# KTIR-FRONT.net
KiCad netlist of a schematic drawn in Altium Designer
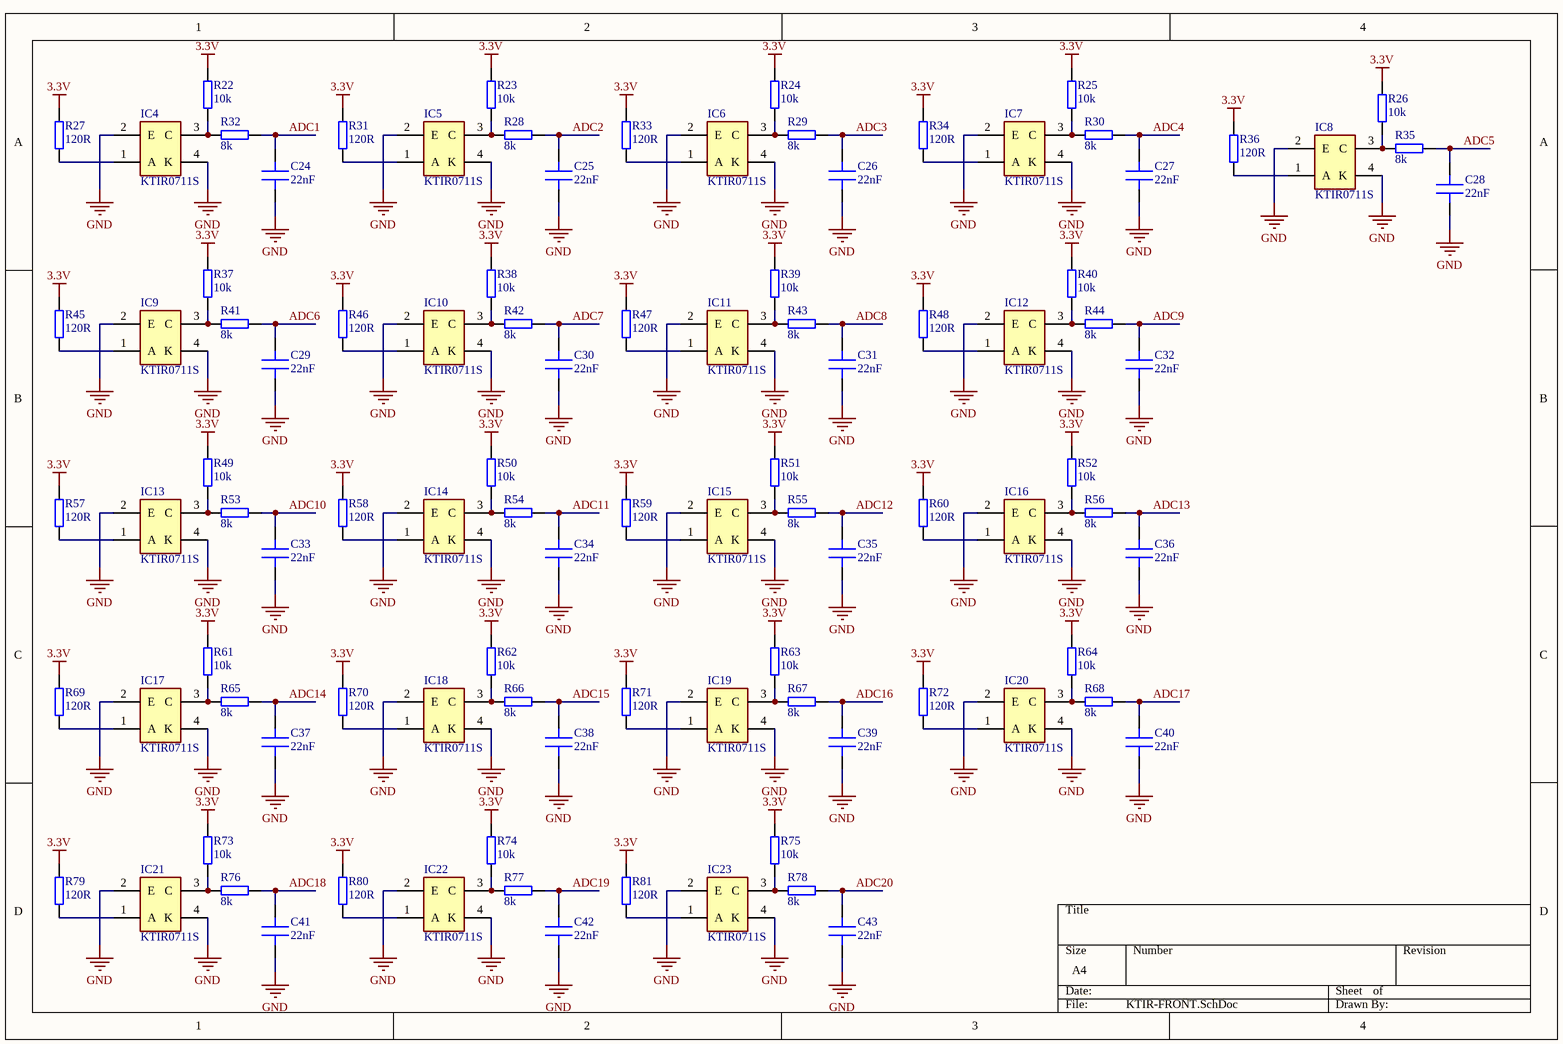
[diagram p0: KTIR-FRONT.SchDoc]

(export (version "E")
  (design (tool "Eeschema 10.0.6"))
  (components
    (comp (ref "C24")
      (value "22nF")
      (footprint "C 0603")
      (description "MLCC Capacitor")
      (libsource (lib "Components") (part "Capacitor"))
    )
    (comp (ref "C25")
      (value "22nF")
      (footprint "C 0603")
      (description "MLCC Capacitor")
      (libsource (lib "Components") (part "Capacitor"))
    )
    (comp (ref "C26")
      (value "22nF")
      (footprint "C 0603")
      (description "MLCC Capacitor")
      (libsource (lib "Components") (part "Capacitor"))
    )
    (comp (ref "C27")
      (value "22nF")
      (footprint "C 0603")
      (description "MLCC Capacitor")
      (libsource (lib "Components") (part "Capacitor"))
    )
    (comp (ref "C28")
      (value "22nF")
      (footprint "C 0603")
      (description "MLCC Capacitor")
      (libsource (lib "Components") (part "Capacitor"))
    )
    (comp (ref "C29")
      (value "22nF")
      (footprint "C 0603")
      (description "MLCC Capacitor")
      (libsource (lib "Components") (part "Capacitor"))
    )
    (comp (ref "C30")
      (value "22nF")
      (footprint "C 0603")
      (description "MLCC Capacitor")
      (libsource (lib "Components") (part "Capacitor"))
    )
    (comp (ref "C31")
      (value "22nF")
      (footprint "C 0603")
      (description "MLCC Capacitor")
      (libsource (lib "Components") (part "Capacitor"))
    )
    (comp (ref "C32")
      (value "22nF")
      (footprint "C 0603")
      (description "MLCC Capacitor")
      (libsource (lib "Components") (part "Capacitor"))
    )
    (comp (ref "C33")
      (value "22nF")
      (footprint "C 0603")
      (description "MLCC Capacitor")
      (libsource (lib "Components") (part "Capacitor"))
    )
    (comp (ref "C34")
      (value "22nF")
      (footprint "C 0603")
      (description "MLCC Capacitor")
      (libsource (lib "Components") (part "Capacitor"))
    )
    (comp (ref "C35")
      (value "22nF")
      (footprint "C 0603")
      (description "MLCC Capacitor")
      (libsource (lib "Components") (part "Capacitor"))
    )
    (comp (ref "C36")
      (value "22nF")
      (footprint "C 0603")
      (description "MLCC Capacitor")
      (libsource (lib "Components") (part "Capacitor"))
    )
    (comp (ref "C37")
      (value "22nF")
      (footprint "C 0603")
      (description "MLCC Capacitor")
      (libsource (lib "Components") (part "Capacitor"))
    )
    (comp (ref "C38")
      (value "22nF")
      (footprint "C 0603")
      (description "MLCC Capacitor")
      (libsource (lib "Components") (part "Capacitor"))
    )
    (comp (ref "C39")
      (value "22nF")
      (footprint "C 0603")
      (description "MLCC Capacitor")
      (libsource (lib "Components") (part "Capacitor"))
    )
    (comp (ref "C40")
      (value "22nF")
      (footprint "C 0603")
      (description "MLCC Capacitor")
      (libsource (lib "Components") (part "Capacitor"))
    )
    (comp (ref "C41")
      (value "22nF")
      (footprint "C 0603")
      (description "MLCC Capacitor")
      (libsource (lib "Components") (part "Capacitor"))
    )
    (comp (ref "C42")
      (value "22nF")
      (footprint "C 0603")
      (description "MLCC Capacitor")
      (libsource (lib "Components") (part "Capacitor"))
    )
    (comp (ref "C43")
      (value "22nF")
      (footprint "C 0603")
      (description "MLCC Capacitor")
      (libsource (lib "Components") (part "Capacitor"))
    )
    (comp (ref "IC4")
      (value "KTIR0711S")
      (footprint "KTIR0711S")
      (description "Integrated Circuit")
      (libsource (lib "lib-all-components") (part "KTIR0711S"))
    )
    (comp (ref "IC5")
      (value "KTIR0711S")
      (footprint "KTIR0711S")
      (description "Integrated Circuit")
      (libsource (lib "lib-all-components") (part "KTIR0711S"))
    )
    (comp (ref "IC6")
      (value "KTIR0711S")
      (footprint "KTIR0711S")
      (description "Integrated Circuit")
      (libsource (lib "lib-all-components") (part "KTIR0711S"))
    )
    (comp (ref "IC7")
      (value "KTIR0711S")
      (footprint "KTIR0711S")
      (description "Integrated Circuit")
      (libsource (lib "lib-all-components") (part "KTIR0711S"))
    )
    (comp (ref "IC8")
      (value "KTIR0711S")
      (footprint "KTIR0711S")
      (description "Integrated Circuit")
      (libsource (lib "lib-all-components") (part "KTIR0711S"))
    )
    (comp (ref "IC9")
      (value "KTIR0711S")
      (footprint "KTIR0711S")
      (description "Integrated Circuit")
      (libsource (lib "lib-all-components") (part "KTIR0711S"))
    )
    (comp (ref "IC10")
      (value "KTIR0711S")
      (footprint "KTIR0711S")
      (description "Integrated Circuit")
      (libsource (lib "lib-all-components") (part "KTIR0711S"))
    )
    (comp (ref "IC11")
      (value "KTIR0711S")
      (footprint "KTIR0711S")
      (description "Integrated Circuit")
      (libsource (lib "lib-all-components") (part "KTIR0711S"))
    )
    (comp (ref "IC12")
      (value "KTIR0711S")
      (footprint "KTIR0711S")
      (description "Integrated Circuit")
      (libsource (lib "lib-all-components") (part "KTIR0711S"))
    )
    (comp (ref "IC13")
      (value "KTIR0711S")
      (footprint "KTIR0711S")
      (description "Integrated Circuit")
      (libsource (lib "lib-all-components") (part "KTIR0711S"))
    )
    (comp (ref "IC14")
      (value "KTIR0711S")
      (footprint "KTIR0711S")
      (description "Integrated Circuit")
      (libsource (lib "lib-all-components") (part "KTIR0711S"))
    )
    (comp (ref "IC15")
      (value "KTIR0711S")
      (footprint "KTIR0711S")
      (description "Integrated Circuit")
      (libsource (lib "lib-all-components") (part "KTIR0711S"))
    )
    (comp (ref "IC16")
      (value "KTIR0711S")
      (footprint "KTIR0711S")
      (description "Integrated Circuit")
      (libsource (lib "lib-all-components") (part "KTIR0711S"))
    )
    (comp (ref "IC17")
      (value "KTIR0711S")
      (footprint "KTIR0711S")
      (description "Integrated Circuit")
      (libsource (lib "lib-all-components") (part "KTIR0711S"))
    )
    (comp (ref "IC18")
      (value "KTIR0711S")
      (footprint "KTIR0711S")
      (description "Integrated Circuit")
      (libsource (lib "lib-all-components") (part "KTIR0711S"))
    )
    (comp (ref "IC19")
      (value "KTIR0711S")
      (footprint "KTIR0711S")
      (description "Integrated Circuit")
      (libsource (lib "lib-all-components") (part "KTIR0711S"))
    )
    (comp (ref "IC20")
      (value "KTIR0711S")
      (footprint "KTIR0711S")
      (description "Integrated Circuit")
      (libsource (lib "lib-all-components") (part "KTIR0711S"))
    )
    (comp (ref "IC21")
      (value "KTIR0711S")
      (footprint "KTIR0711S")
      (description "Integrated Circuit")
      (libsource (lib "lib-all-components") (part "KTIR0711S"))
    )
    (comp (ref "IC22")
      (value "KTIR0711S")
      (footprint "KTIR0711S")
      (description "Integrated Circuit")
      (libsource (lib "lib-all-components") (part "KTIR0711S"))
    )
    (comp (ref "IC23")
      (value "KTIR0711S")
      (footprint "KTIR0711S")
      (description "Integrated Circuit")
      (libsource (lib "lib-all-components") (part "KTIR0711S"))
    )
    (comp (ref "R22")
      (value "10k")
      (footprint "R 0603")
      (description "General pourpouse resistor")
      (libsource (lib "Components") (part "Resistor"))
    )
    (comp (ref "R23")
      (value "10k")
      (footprint "R 0603")
      (description "General pourpouse resistor")
      (libsource (lib "Components") (part "Resistor"))
    )
    (comp (ref "R24")
      (value "10k")
      (footprint "R 0603")
      (description "General pourpouse resistor")
      (libsource (lib "Components") (part "Resistor"))
    )
    (comp (ref "R25")
      (value "10k")
      (footprint "R 0603")
      (description "General pourpouse resistor")
      (libsource (lib "Components") (part "Resistor"))
    )
    (comp (ref "R26")
      (value "10k")
      (footprint "R 0603")
      (description "General pourpouse resistor")
      (libsource (lib "Components") (part "Resistor"))
    )
    (comp (ref "R27")
      (value "120R")
      (footprint "R 0603")
      (description "General pourpouse resistor")
      (libsource (lib "Components") (part "Resistor"))
    )
    (comp (ref "R28")
      (value "8k")
      (footprint "R 0603")
      (description "General pourpouse resistor")
      (libsource (lib "Components") (part "Resistor"))
    )
    (comp (ref "R29")
      (value "8k")
      (footprint "R 0603")
      (description "General pourpouse resistor")
      (libsource (lib "Components") (part "Resistor"))
    )
    (comp (ref "R30")
      (value "8k")
      (footprint "R 0603")
      (description "General pourpouse resistor")
      (libsource (lib "Components") (part "Resistor"))
    )
    (comp (ref "R31")
      (value "120R")
      (footprint "R 0603")
      (description "General pourpouse resistor")
      (libsource (lib "Components") (part "Resistor"))
    )
    (comp (ref "R32")
      (value "8k")
      (footprint "R 0603")
      (description "General pourpouse resistor")
      (libsource (lib "Components") (part "Resistor"))
    )
    (comp (ref "R33")
      (value "120R")
      (footprint "R 0603")
      (description "General pourpouse resistor")
      (libsource (lib "Components") (part "Resistor"))
    )
    (comp (ref "R34")
      (value "120R")
      (footprint "R 0603")
      (description "General pourpouse resistor")
      (libsource (lib "Components") (part "Resistor"))
    )
    (comp (ref "R35")
      (value "8k")
      (footprint "R 0603")
      (description "General pourpouse resistor")
      (libsource (lib "Components") (part "Resistor"))
    )
    (comp (ref "R36")
      (value "120R")
      (footprint "R 0603")
      (description "General pourpouse resistor")
      (libsource (lib "Components") (part "Resistor"))
    )
    (comp (ref "R37")
      (value "10k")
      (footprint "R 0603")
      (description "General pourpouse resistor")
      (libsource (lib "Components") (part "Resistor"))
    )
    (comp (ref "R38")
      (value "10k")
      (footprint "R 0603")
      (description "General pourpouse resistor")
      (libsource (lib "Components") (part "Resistor"))
    )
    (comp (ref "R39")
      (value "10k")
      (footprint "R 0603")
      (description "General pourpouse resistor")
      (libsource (lib "Components") (part "Resistor"))
    )
    (comp (ref "R40")
      (value "10k")
      (footprint "R 0603")
      (description "General pourpouse resistor")
      (libsource (lib "Components") (part "Resistor"))
    )
    (comp (ref "R41")
      (value "8k")
      (footprint "R 0603")
      (description "General pourpouse resistor")
      (libsource (lib "Components") (part "Resistor"))
    )
    (comp (ref "R42")
      (value "8k")
      (footprint "R 0603")
      (description "General pourpouse resistor")
      (libsource (lib "Components") (part "Resistor"))
    )
    (comp (ref "R43")
      (value "8k")
      (footprint "R 0603")
      (description "General pourpouse resistor")
      (libsource (lib "Components") (part "Resistor"))
    )
    (comp (ref "R44")
      (value "8k")
      (footprint "R 0603")
      (description "General pourpouse resistor")
      (libsource (lib "Components") (part "Resistor"))
    )
    (comp (ref "R45")
      (value "120R")
      (footprint "R 0603")
      (description "General pourpouse resistor")
      (libsource (lib "Components") (part "Resistor"))
    )
    (comp (ref "R46")
      (value "120R")
      (footprint "R 0603")
      (description "General pourpouse resistor")
      (libsource (lib "Components") (part "Resistor"))
    )
    (comp (ref "R47")
      (value "120R")
      (footprint "R 0603")
      (description "General pourpouse resistor")
      (libsource (lib "Components") (part "Resistor"))
    )
    (comp (ref "R48")
      (value "120R")
      (footprint "R 0603")
      (description "General pourpouse resistor")
      (libsource (lib "Components") (part "Resistor"))
    )
    (comp (ref "R49")
      (value "10k")
      (footprint "R 0603")
      (description "General pourpouse resistor")
      (libsource (lib "Components") (part "Resistor"))
    )
    (comp (ref "R50")
      (value "10k")
      (footprint "R 0603")
      (description "General pourpouse resistor")
      (libsource (lib "Components") (part "Resistor"))
    )
    (comp (ref "R51")
      (value "10k")
      (footprint "R 0603")
      (description "General pourpouse resistor")
      (libsource (lib "Components") (part "Resistor"))
    )
    (comp (ref "R52")
      (value "10k")
      (footprint "R 0603")
      (description "General pourpouse resistor")
      (libsource (lib "Components") (part "Resistor"))
    )
    (comp (ref "R53")
      (value "8k")
      (footprint "R 0603")
      (description "General pourpouse resistor")
      (libsource (lib "Components") (part "Resistor"))
    )
    (comp (ref "R54")
      (value "8k")
      (footprint "R 0603")
      (description "General pourpouse resistor")
      (libsource (lib "Components") (part "Resistor"))
    )
    (comp (ref "R55")
      (value "8k")
      (footprint "R 0603")
      (description "General pourpouse resistor")
      (libsource (lib "Components") (part "Resistor"))
    )
    (comp (ref "R56")
      (value "8k")
      (footprint "R 0603")
      (description "General pourpouse resistor")
      (libsource (lib "Components") (part "Resistor"))
    )
    (comp (ref "R57")
      (value "120R")
      (footprint "R 0603")
      (description "General pourpouse resistor")
      (libsource (lib "Components") (part "Resistor"))
    )
    (comp (ref "R58")
      (value "120R")
      (footprint "R 0603")
      (description "General pourpouse resistor")
      (libsource (lib "Components") (part "Resistor"))
    )
    (comp (ref "R59")
      (value "120R")
      (footprint "R 0603")
      (description "General pourpouse resistor")
      (libsource (lib "Components") (part "Resistor"))
    )
    (comp (ref "R60")
      (value "120R")
      (footprint "R 0603")
      (description "General pourpouse resistor")
      (libsource (lib "Components") (part "Resistor"))
    )
    (comp (ref "R61")
      (value "10k")
      (footprint "R 0603")
      (description "General pourpouse resistor")
      (libsource (lib "Components") (part "Resistor"))
    )
    (comp (ref "R62")
      (value "10k")
      (footprint "R 0603")
      (description "General pourpouse resistor")
      (libsource (lib "Components") (part "Resistor"))
    )
    (comp (ref "R63")
      (value "10k")
      (footprint "R 0603")
      (description "General pourpouse resistor")
      (libsource (lib "Components") (part "Resistor"))
    )
    (comp (ref "R64")
      (value "10k")
      (footprint "R 0603")
      (description "General pourpouse resistor")
      (libsource (lib "Components") (part "Resistor"))
    )
    (comp (ref "R65")
      (value "8k")
      (footprint "R 0603")
      (description "General pourpouse resistor")
      (libsource (lib "Components") (part "Resistor"))
    )
    (comp (ref "R66")
      (value "8k")
      (footprint "R 0603")
      (description "General pourpouse resistor")
      (libsource (lib "Components") (part "Resistor"))
    )
    (comp (ref "R67")
      (value "8k")
      (footprint "R 0603")
      (description "General pourpouse resistor")
      (libsource (lib "Components") (part "Resistor"))
    )
    (comp (ref "R68")
      (value "8k")
      (footprint "R 0603")
      (description "General pourpouse resistor")
      (libsource (lib "Components") (part "Resistor"))
    )
    (comp (ref "R69")
      (value "120R")
      (footprint "R 0603")
      (description "General pourpouse resistor")
      (libsource (lib "Components") (part "Resistor"))
    )
    (comp (ref "R70")
      (value "120R")
      (footprint "R 0603")
      (description "General pourpouse resistor")
      (libsource (lib "Components") (part "Resistor"))
    )
    (comp (ref "R71")
      (value "120R")
      (footprint "R 0603")
      (description "General pourpouse resistor")
      (libsource (lib "Components") (part "Resistor"))
    )
    (comp (ref "R72")
      (value "120R")
      (footprint "R 0603")
      (description "General pourpouse resistor")
      (libsource (lib "Components") (part "Resistor"))
    )
    (comp (ref "R73")
      (value "10k")
      (footprint "R 0603")
      (description "General pourpouse resistor")
      (libsource (lib "Components") (part "Resistor"))
    )
    (comp (ref "R74")
      (value "10k")
      (footprint "R 0603")
      (description "General pourpouse resistor")
      (libsource (lib "Components") (part "Resistor"))
    )
    (comp (ref "R75")
      (value "10k")
      (footprint "R 0603")
      (description "General pourpouse resistor")
      (libsource (lib "Components") (part "Resistor"))
    )
    (comp (ref "R76")
      (value "8k")
      (footprint "R 0603")
      (description "General pourpouse resistor")
      (libsource (lib "Components") (part "Resistor"))
    )
    (comp (ref "R77")
      (value "8k")
      (footprint "R 0603")
      (description "General pourpouse resistor")
      (libsource (lib "Components") (part "Resistor"))
    )
    (comp (ref "R78")
      (value "8k")
      (footprint "R 0603")
      (description "General pourpouse resistor")
      (libsource (lib "Components") (part "Resistor"))
    )
    (comp (ref "R79")
      (value "120R")
      (footprint "R 0603")
      (description "General pourpouse resistor")
      (libsource (lib "Components") (part "Resistor"))
    )
    (comp (ref "R80")
      (value "120R")
      (footprint "R 0603")
      (description "General pourpouse resistor")
      (libsource (lib "Components") (part "Resistor"))
    )
    (comp (ref "R81")
      (value "120R")
      (footprint "R 0603")
      (description "General pourpouse resistor")
      (libsource (lib "Components") (part "Resistor"))
    )
  )
  (nets
    (net (code "1") (name "/ADC1") (class "Default")
      (node (ref "C24") (pin "1") (pinfunction "1_1") (pintype "passive"))
      (node (ref "R32") (pin "1") (pinfunction "1_1") (pintype "passive"))
    )
    (net (code "2") (name "/ADC2") (class "Default")
      (node (ref "C25") (pin "1") (pinfunction "1_1") (pintype "passive"))
      (node (ref "R28") (pin "1") (pinfunction "1_1") (pintype "passive"))
    )
    (net (code "3") (name "/ADC3") (class "Default")
      (node (ref "C26") (pin "1") (pinfunction "1_1") (pintype "passive"))
      (node (ref "R29") (pin "1") (pinfunction "1_1") (pintype "passive"))
    )
    (net (code "4") (name "/ADC4") (class "Default")
      (node (ref "C27") (pin "1") (pinfunction "1_1") (pintype "passive"))
      (node (ref "R30") (pin "1") (pinfunction "1_1") (pintype "passive"))
    )
    (net (code "5") (name "/ADC5") (class "Default")
      (node (ref "C28") (pin "1") (pinfunction "1_1") (pintype "passive"))
      (node (ref "R35") (pin "1") (pinfunction "1_1") (pintype "passive"))
    )
    (net (code "6") (name "/ADC6") (class "Default")
      (node (ref "C29") (pin "1") (pinfunction "1_1") (pintype "passive"))
      (node (ref "R41") (pin "1") (pinfunction "1_1") (pintype "passive"))
    )
    (net (code "7") (name "/ADC7") (class "Default")
      (node (ref "C30") (pin "1") (pinfunction "1_1") (pintype "passive"))
      (node (ref "R42") (pin "1") (pinfunction "1_1") (pintype "passive"))
    )
    (net (code "8") (name "/ADC8") (class "Default")
      (node (ref "C31") (pin "1") (pinfunction "1_1") (pintype "passive"))
      (node (ref "R43") (pin "1") (pinfunction "1_1") (pintype "passive"))
    )
    (net (code "9") (name "/ADC9") (class "Default")
      (node (ref "C32") (pin "1") (pinfunction "1_1") (pintype "passive"))
      (node (ref "R44") (pin "1") (pinfunction "1_1") (pintype "passive"))
    )
    (net (code "10") (name "/ADC10") (class "Default")
      (node (ref "C33") (pin "1") (pinfunction "1_1") (pintype "passive"))
      (node (ref "R53") (pin "1") (pinfunction "1_1") (pintype "passive"))
    )
    (net (code "11") (name "/ADC11") (class "Default")
      (node (ref "C34") (pin "1") (pinfunction "1_1") (pintype "passive"))
      (node (ref "R54") (pin "1") (pinfunction "1_1") (pintype "passive"))
    )
    (net (code "12") (name "/ADC12") (class "Default")
      (node (ref "C35") (pin "1") (pinfunction "1_1") (pintype "passive"))
      (node (ref "R55") (pin "1") (pinfunction "1_1") (pintype "passive"))
    )
    (net (code "13") (name "/ADC13") (class "Default")
      (node (ref "C36") (pin "1") (pinfunction "1_1") (pintype "passive"))
      (node (ref "R56") (pin "1") (pinfunction "1_1") (pintype "passive"))
    )
    (net (code "14") (name "/ADC14") (class "Default")
      (node (ref "C37") (pin "1") (pinfunction "1_1") (pintype "passive"))
      (node (ref "R65") (pin "1") (pinfunction "1_1") (pintype "passive"))
    )
    (net (code "15") (name "/ADC15") (class "Default")
      (node (ref "C38") (pin "1") (pinfunction "1_1") (pintype "passive"))
      (node (ref "R66") (pin "1") (pinfunction "1_1") (pintype "passive"))
    )
    (net (code "16") (name "/ADC16") (class "Default")
      (node (ref "C39") (pin "1") (pinfunction "1_1") (pintype "passive"))
      (node (ref "R67") (pin "1") (pinfunction "1_1") (pintype "passive"))
    )
    (net (code "17") (name "/ADC17") (class "Default")
      (node (ref "C40") (pin "1") (pinfunction "1_1") (pintype "passive"))
      (node (ref "R68") (pin "1") (pinfunction "1_1") (pintype "passive"))
    )
    (net (code "18") (name "/ADC18") (class "Default")
      (node (ref "C41") (pin "1") (pinfunction "1_1") (pintype "passive"))
      (node (ref "R76") (pin "1") (pinfunction "1_1") (pintype "passive"))
    )
    (net (code "19") (name "/ADC19") (class "Default")
      (node (ref "C42") (pin "1") (pinfunction "1_1") (pintype "passive"))
      (node (ref "R77") (pin "1") (pinfunction "1_1") (pintype "passive"))
    )
    (net (code "20") (name "/ADC20") (class "Default")
      (node (ref "C43") (pin "1") (pinfunction "1_1") (pintype "passive"))
      (node (ref "R78") (pin "1") (pinfunction "1_1") (pintype "passive"))
    )
    (net (code "21") (name "3.3V") (class "Default")
      (node (ref "R22") (pin "1") (pinfunction "1_1") (pintype "passive"))
      (node (ref "R23") (pin "1") (pinfunction "1_1") (pintype "passive"))
      (node (ref "R24") (pin "1") (pinfunction "1_1") (pintype "passive"))
      (node (ref "R25") (pin "1") (pinfunction "1_1") (pintype "passive"))
      (node (ref "R26") (pin "1") (pinfunction "1_1") (pintype "passive"))
      (node (ref "R27") (pin "1") (pinfunction "1_1") (pintype "passive"))
      (node (ref "R31") (pin "1") (pinfunction "1_1") (pintype "passive"))
      (node (ref "R33") (pin "1") (pinfunction "1_1") (pintype "passive"))
      (node (ref "R34") (pin "1") (pinfunction "1_1") (pintype "passive"))
      (node (ref "R36") (pin "1") (pinfunction "1_1") (pintype "passive"))
      (node (ref "R37") (pin "1") (pinfunction "1_1") (pintype "passive"))
      (node (ref "R38") (pin "1") (pinfunction "1_1") (pintype "passive"))
      (node (ref "R39") (pin "1") (pinfunction "1_1") (pintype "passive"))
      (node (ref "R40") (pin "1") (pinfunction "1_1") (pintype "passive"))
      (node (ref "R45") (pin "1") (pinfunction "1_1") (pintype "passive"))
      (node (ref "R46") (pin "1") (pinfunction "1_1") (pintype "passive"))
      (node (ref "R47") (pin "1") (pinfunction "1_1") (pintype "passive"))
      (node (ref "R48") (pin "1") (pinfunction "1_1") (pintype "passive"))
      (node (ref "R49") (pin "1") (pinfunction "1_1") (pintype "passive"))
      (node (ref "R50") (pin "1") (pinfunction "1_1") (pintype "passive"))
      (node (ref "R51") (pin "1") (pinfunction "1_1") (pintype "passive"))
      (node (ref "R52") (pin "1") (pinfunction "1_1") (pintype "passive"))
      (node (ref "R57") (pin "1") (pinfunction "1_1") (pintype "passive"))
      (node (ref "R58") (pin "1") (pinfunction "1_1") (pintype "passive"))
      (node (ref "R59") (pin "1") (pinfunction "1_1") (pintype "passive"))
      (node (ref "R60") (pin "1") (pinfunction "1_1") (pintype "passive"))
      (node (ref "R61") (pin "1") (pinfunction "1_1") (pintype "passive"))
      (node (ref "R62") (pin "1") (pinfunction "1_1") (pintype "passive"))
      (node (ref "R63") (pin "1") (pinfunction "1_1") (pintype "passive"))
      (node (ref "R64") (pin "1") (pinfunction "1_1") (pintype "passive"))
      (node (ref "R69") (pin "1") (pinfunction "1_1") (pintype "passive"))
      (node (ref "R70") (pin "1") (pinfunction "1_1") (pintype "passive"))
      (node (ref "R71") (pin "1") (pinfunction "1_1") (pintype "passive"))
      (node (ref "R72") (pin "1") (pinfunction "1_1") (pintype "passive"))
      (node (ref "R73") (pin "1") (pinfunction "1_1") (pintype "passive"))
      (node (ref "R74") (pin "1") (pinfunction "1_1") (pintype "passive"))
      (node (ref "R75") (pin "1") (pinfunction "1_1") (pintype "passive"))
      (node (ref "R79") (pin "1") (pinfunction "1_1") (pintype "passive"))
      (node (ref "R80") (pin "1") (pinfunction "1_1") (pintype "passive"))
      (node (ref "R81") (pin "1") (pinfunction "1_1") (pintype "passive"))
    )
    (net (code "22") (name "GND") (class "Default")
      (node (ref "C24") (pin "2") (pinfunction "2_2") (pintype "passive"))
      (node (ref "C25") (pin "2") (pinfunction "2_2") (pintype "passive"))
      (node (ref "C26") (pin "2") (pinfunction "2_2") (pintype "passive"))
      (node (ref "C27") (pin "2") (pinfunction "2_2") (pintype "passive"))
      (node (ref "C28") (pin "2") (pinfunction "2_2") (pintype "passive"))
      (node (ref "C29") (pin "2") (pinfunction "2_2") (pintype "passive"))
      (node (ref "C30") (pin "2") (pinfunction "2_2") (pintype "passive"))
      (node (ref "C31") (pin "2") (pinfunction "2_2") (pintype "passive"))
      (node (ref "C32") (pin "2") (pinfunction "2_2") (pintype "passive"))
      (node (ref "C33") (pin "2") (pinfunction "2_2") (pintype "passive"))
      (node (ref "C34") (pin "2") (pinfunction "2_2") (pintype "passive"))
      (node (ref "C35") (pin "2") (pinfunction "2_2") (pintype "passive"))
      (node (ref "C36") (pin "2") (pinfunction "2_2") (pintype "passive"))
      (node (ref "C37") (pin "2") (pinfunction "2_2") (pintype "passive"))
      (node (ref "C38") (pin "2") (pinfunction "2_2") (pintype "passive"))
      (node (ref "C39") (pin "2") (pinfunction "2_2") (pintype "passive"))
      (node (ref "C40") (pin "2") (pinfunction "2_2") (pintype "passive"))
      (node (ref "C41") (pin "2") (pinfunction "2_2") (pintype "passive"))
      (node (ref "C42") (pin "2") (pinfunction "2_2") (pintype "passive"))
      (node (ref "C43") (pin "2") (pinfunction "2_2") (pintype "passive"))
      (node (ref "IC10") (pin "2") (pinfunction "E_2") (pintype "passive"))
      (node (ref "IC10") (pin "4") (pinfunction "K_4") (pintype "passive"))
      (node (ref "IC11") (pin "2") (pinfunction "E_2") (pintype "passive"))
      (node (ref "IC11") (pin "4") (pinfunction "K_4") (pintype "passive"))
      (node (ref "IC12") (pin "2") (pinfunction "E_2") (pintype "passive"))
      (node (ref "IC12") (pin "4") (pinfunction "K_4") (pintype "passive"))
      (node (ref "IC13") (pin "2") (pinfunction "E_2") (pintype "passive"))
      (node (ref "IC13") (pin "4") (pinfunction "K_4") (pintype "passive"))
      (node (ref "IC14") (pin "2") (pinfunction "E_2") (pintype "passive"))
      (node (ref "IC14") (pin "4") (pinfunction "K_4") (pintype "passive"))
      (node (ref "IC15") (pin "2") (pinfunction "E_2") (pintype "passive"))
      (node (ref "IC15") (pin "4") (pinfunction "K_4") (pintype "passive"))
      (node (ref "IC16") (pin "2") (pinfunction "E_2") (pintype "passive"))
      (node (ref "IC16") (pin "4") (pinfunction "K_4") (pintype "passive"))
      (node (ref "IC17") (pin "2") (pinfunction "E_2") (pintype "passive"))
      (node (ref "IC17") (pin "4") (pinfunction "K_4") (pintype "passive"))
      (node (ref "IC18") (pin "2") (pinfunction "E_2") (pintype "passive"))
      (node (ref "IC18") (pin "4") (pinfunction "K_4") (pintype "passive"))
      (node (ref "IC19") (pin "2") (pinfunction "E_2") (pintype "passive"))
      (node (ref "IC19") (pin "4") (pinfunction "K_4") (pintype "passive"))
      (node (ref "IC20") (pin "2") (pinfunction "E_2") (pintype "passive"))
      (node (ref "IC20") (pin "4") (pinfunction "K_4") (pintype "passive"))
      (node (ref "IC21") (pin "2") (pinfunction "E_2") (pintype "passive"))
      (node (ref "IC21") (pin "4") (pinfunction "K_4") (pintype "passive"))
      (node (ref "IC22") (pin "2") (pinfunction "E_2") (pintype "passive"))
      (node (ref "IC22") (pin "4") (pinfunction "K_4") (pintype "passive"))
      (node (ref "IC23") (pin "2") (pinfunction "E_2") (pintype "passive"))
      (node (ref "IC23") (pin "4") (pinfunction "K_4") (pintype "passive"))
      (node (ref "IC4") (pin "2") (pinfunction "E_2") (pintype "passive"))
      (node (ref "IC4") (pin "4") (pinfunction "K_4") (pintype "passive"))
      (node (ref "IC5") (pin "2") (pinfunction "E_2") (pintype "passive"))
      (node (ref "IC5") (pin "4") (pinfunction "K_4") (pintype "passive"))
      (node (ref "IC6") (pin "2") (pinfunction "E_2") (pintype "passive"))
      (node (ref "IC6") (pin "4") (pinfunction "K_4") (pintype "passive"))
      (node (ref "IC7") (pin "2") (pinfunction "E_2") (pintype "passive"))
      (node (ref "IC7") (pin "4") (pinfunction "K_4") (pintype "passive"))
      (node (ref "IC8") (pin "2") (pinfunction "E_2") (pintype "passive"))
      (node (ref "IC8") (pin "4") (pinfunction "K_4") (pintype "passive"))
      (node (ref "IC9") (pin "2") (pinfunction "E_2") (pintype "passive"))
      (node (ref "IC9") (pin "4") (pinfunction "K_4") (pintype "passive"))
    )
    (net (code "23") (name "Net-(IC4-A)") (class "Default")
      (node (ref "IC4") (pin "1") (pinfunction "A_1") (pintype "passive"))
      (node (ref "R27") (pin "2") (pinfunction "2_2") (pintype "passive"))
    )
    (net (code "24") (name "Net-(IC4-C)") (class "Default")
      (node (ref "IC4") (pin "3") (pinfunction "C_3") (pintype "passive"))
      (node (ref "R22") (pin "2") (pinfunction "2_2") (pintype "passive"))
      (node (ref "R32") (pin "2") (pinfunction "2_2") (pintype "passive"))
    )
    (net (code "25") (name "Net-(IC5-A)") (class "Default")
      (node (ref "IC5") (pin "1") (pinfunction "A_1") (pintype "passive"))
      (node (ref "R31") (pin "2") (pinfunction "2_2") (pintype "passive"))
    )
    (net (code "26") (name "Net-(IC5-C)") (class "Default")
      (node (ref "IC5") (pin "3") (pinfunction "C_3") (pintype "passive"))
      (node (ref "R23") (pin "2") (pinfunction "2_2") (pintype "passive"))
      (node (ref "R28") (pin "2") (pinfunction "2_2") (pintype "passive"))
    )
    (net (code "27") (name "Net-(IC6-A)") (class "Default")
      (node (ref "IC6") (pin "1") (pinfunction "A_1") (pintype "passive"))
      (node (ref "R33") (pin "2") (pinfunction "2_2") (pintype "passive"))
    )
    (net (code "28") (name "Net-(IC6-C)") (class "Default")
      (node (ref "IC6") (pin "3") (pinfunction "C_3") (pintype "passive"))
      (node (ref "R24") (pin "2") (pinfunction "2_2") (pintype "passive"))
      (node (ref "R29") (pin "2") (pinfunction "2_2") (pintype "passive"))
    )
    (net (code "29") (name "Net-(IC7-A)") (class "Default")
      (node (ref "IC7") (pin "1") (pinfunction "A_1") (pintype "passive"))
      (node (ref "R34") (pin "2") (pinfunction "2_2") (pintype "passive"))
    )
    (net (code "30") (name "Net-(IC7-C)") (class "Default")
      (node (ref "IC7") (pin "3") (pinfunction "C_3") (pintype "passive"))
      (node (ref "R25") (pin "2") (pinfunction "2_2") (pintype "passive"))
      (node (ref "R30") (pin "2") (pinfunction "2_2") (pintype "passive"))
    )
    (net (code "31") (name "Net-(IC8-A)") (class "Default")
      (node (ref "IC8") (pin "1") (pinfunction "A_1") (pintype "passive"))
      (node (ref "R36") (pin "2") (pinfunction "2_2") (pintype "passive"))
    )
    (net (code "32") (name "Net-(IC8-C)") (class "Default")
      (node (ref "IC8") (pin "3") (pinfunction "C_3") (pintype "passive"))
      (node (ref "R26") (pin "2") (pinfunction "2_2") (pintype "passive"))
      (node (ref "R35") (pin "2") (pinfunction "2_2") (pintype "passive"))
    )
    (net (code "33") (name "Net-(IC9-A)") (class "Default")
      (node (ref "IC9") (pin "1") (pinfunction "A_1") (pintype "passive"))
      (node (ref "R45") (pin "2") (pinfunction "2_2") (pintype "passive"))
    )
    (net (code "34") (name "Net-(IC9-C)") (class "Default")
      (node (ref "IC9") (pin "3") (pinfunction "C_3") (pintype "passive"))
      (node (ref "R37") (pin "2") (pinfunction "2_2") (pintype "passive"))
      (node (ref "R41") (pin "2") (pinfunction "2_2") (pintype "passive"))
    )
    (net (code "35") (name "Net-(IC10-A)") (class "Default")
      (node (ref "IC10") (pin "1") (pinfunction "A_1") (pintype "passive"))
      (node (ref "R46") (pin "2") (pinfunction "2_2") (pintype "passive"))
    )
    (net (code "36") (name "Net-(IC10-C)") (class "Default")
      (node (ref "IC10") (pin "3") (pinfunction "C_3") (pintype "passive"))
      (node (ref "R38") (pin "2") (pinfunction "2_2") (pintype "passive"))
      (node (ref "R42") (pin "2") (pinfunction "2_2") (pintype "passive"))
    )
    (net (code "37") (name "Net-(IC11-A)") (class "Default")
      (node (ref "IC11") (pin "1") (pinfunction "A_1") (pintype "passive"))
      (node (ref "R47") (pin "2") (pinfunction "2_2") (pintype "passive"))
    )
    (net (code "38") (name "Net-(IC11-C)") (class "Default")
      (node (ref "IC11") (pin "3") (pinfunction "C_3") (pintype "passive"))
      (node (ref "R39") (pin "2") (pinfunction "2_2") (pintype "passive"))
      (node (ref "R43") (pin "2") (pinfunction "2_2") (pintype "passive"))
    )
    (net (code "39") (name "Net-(IC12-A)") (class "Default")
      (node (ref "IC12") (pin "1") (pinfunction "A_1") (pintype "passive"))
      (node (ref "R48") (pin "2") (pinfunction "2_2") (pintype "passive"))
    )
    (net (code "40") (name "Net-(IC12-C)") (class "Default")
      (node (ref "IC12") (pin "3") (pinfunction "C_3") (pintype "passive"))
      (node (ref "R40") (pin "2") (pinfunction "2_2") (pintype "passive"))
      (node (ref "R44") (pin "2") (pinfunction "2_2") (pintype "passive"))
    )
    (net (code "41") (name "Net-(IC13-A)") (class "Default")
      (node (ref "IC13") (pin "1") (pinfunction "A_1") (pintype "passive"))
      (node (ref "R57") (pin "2") (pinfunction "2_2") (pintype "passive"))
    )
    (net (code "42") (name "Net-(IC13-C)") (class "Default")
      (node (ref "IC13") (pin "3") (pinfunction "C_3") (pintype "passive"))
      (node (ref "R49") (pin "2") (pinfunction "2_2") (pintype "passive"))
      (node (ref "R53") (pin "2") (pinfunction "2_2") (pintype "passive"))
    )
    (net (code "43") (name "Net-(IC14-A)") (class "Default")
      (node (ref "IC14") (pin "1") (pinfunction "A_1") (pintype "passive"))
      (node (ref "R58") (pin "2") (pinfunction "2_2") (pintype "passive"))
    )
    (net (code "44") (name "Net-(IC14-C)") (class "Default")
      (node (ref "IC14") (pin "3") (pinfunction "C_3") (pintype "passive"))
      (node (ref "R50") (pin "2") (pinfunction "2_2") (pintype "passive"))
      (node (ref "R54") (pin "2") (pinfunction "2_2") (pintype "passive"))
    )
    (net (code "45") (name "Net-(IC15-A)") (class "Default")
      (node (ref "IC15") (pin "1") (pinfunction "A_1") (pintype "passive"))
      (node (ref "R59") (pin "2") (pinfunction "2_2") (pintype "passive"))
    )
    (net (code "46") (name "Net-(IC15-C)") (class "Default")
      (node (ref "IC15") (pin "3") (pinfunction "C_3") (pintype "passive"))
      (node (ref "R51") (pin "2") (pinfunction "2_2") (pintype "passive"))
      (node (ref "R55") (pin "2") (pinfunction "2_2") (pintype "passive"))
    )
    (net (code "47") (name "Net-(IC16-A)") (class "Default")
      (node (ref "IC16") (pin "1") (pinfunction "A_1") (pintype "passive"))
      (node (ref "R60") (pin "2") (pinfunction "2_2") (pintype "passive"))
    )
    (net (code "48") (name "Net-(IC16-C)") (class "Default")
      (node (ref "IC16") (pin "3") (pinfunction "C_3") (pintype "passive"))
      (node (ref "R52") (pin "2") (pinfunction "2_2") (pintype "passive"))
      (node (ref "R56") (pin "2") (pinfunction "2_2") (pintype "passive"))
    )
    (net (code "49") (name "Net-(IC17-A)") (class "Default")
      (node (ref "IC17") (pin "1") (pinfunction "A_1") (pintype "passive"))
      (node (ref "R69") (pin "2") (pinfunction "2_2") (pintype "passive"))
    )
    (net (code "50") (name "Net-(IC17-C)") (class "Default")
      (node (ref "IC17") (pin "3") (pinfunction "C_3") (pintype "passive"))
      (node (ref "R61") (pin "2") (pinfunction "2_2") (pintype "passive"))
      (node (ref "R65") (pin "2") (pinfunction "2_2") (pintype "passive"))
    )
    (net (code "51") (name "Net-(IC18-A)") (class "Default")
      (node (ref "IC18") (pin "1") (pinfunction "A_1") (pintype "passive"))
      (node (ref "R70") (pin "2") (pinfunction "2_2") (pintype "passive"))
    )
    (net (code "52") (name "Net-(IC18-C)") (class "Default")
      (node (ref "IC18") (pin "3") (pinfunction "C_3") (pintype "passive"))
      (node (ref "R62") (pin "2") (pinfunction "2_2") (pintype "passive"))
      (node (ref "R66") (pin "2") (pinfunction "2_2") (pintype "passive"))
    )
    (net (code "53") (name "Net-(IC19-A)") (class "Default")
      (node (ref "IC19") (pin "1") (pinfunction "A_1") (pintype "passive"))
      (node (ref "R71") (pin "2") (pinfunction "2_2") (pintype "passive"))
    )
    (net (code "54") (name "Net-(IC19-C)") (class "Default")
      (node (ref "IC19") (pin "3") (pinfunction "C_3") (pintype "passive"))
      (node (ref "R63") (pin "2") (pinfunction "2_2") (pintype "passive"))
      (node (ref "R67") (pin "2") (pinfunction "2_2") (pintype "passive"))
    )
    (net (code "55") (name "Net-(IC20-A)") (class "Default")
      (node (ref "IC20") (pin "1") (pinfunction "A_1") (pintype "passive"))
      (node (ref "R72") (pin "2") (pinfunction "2_2") (pintype "passive"))
    )
    (net (code "56") (name "Net-(IC20-C)") (class "Default")
      (node (ref "IC20") (pin "3") (pinfunction "C_3") (pintype "passive"))
      (node (ref "R64") (pin "2") (pinfunction "2_2") (pintype "passive"))
      (node (ref "R68") (pin "2") (pinfunction "2_2") (pintype "passive"))
    )
    (net (code "57") (name "Net-(IC21-A)") (class "Default")
      (node (ref "IC21") (pin "1") (pinfunction "A_1") (pintype "passive"))
      (node (ref "R79") (pin "2") (pinfunction "2_2") (pintype "passive"))
    )
    (net (code "58") (name "Net-(IC21-C)") (class "Default")
      (node (ref "IC21") (pin "3") (pinfunction "C_3") (pintype "passive"))
      (node (ref "R73") (pin "2") (pinfunction "2_2") (pintype "passive"))
      (node (ref "R76") (pin "2") (pinfunction "2_2") (pintype "passive"))
    )
    (net (code "59") (name "Net-(IC22-A)") (class "Default")
      (node (ref "IC22") (pin "1") (pinfunction "A_1") (pintype "passive"))
      (node (ref "R80") (pin "2") (pinfunction "2_2") (pintype "passive"))
    )
    (net (code "60") (name "Net-(IC22-C)") (class "Default")
      (node (ref "IC22") (pin "3") (pinfunction "C_3") (pintype "passive"))
      (node (ref "R74") (pin "2") (pinfunction "2_2") (pintype "passive"))
      (node (ref "R77") (pin "2") (pinfunction "2_2") (pintype "passive"))
    )
    (net (code "61") (name "Net-(IC23-A)") (class "Default")
      (node (ref "IC23") (pin "1") (pinfunction "A_1") (pintype "passive"))
      (node (ref "R81") (pin "2") (pinfunction "2_2") (pintype "passive"))
    )
    (net (code "62") (name "Net-(IC23-C)") (class "Default")
      (node (ref "IC23") (pin "3") (pinfunction "C_3") (pintype "passive"))
      (node (ref "R75") (pin "2") (pinfunction "2_2") (pintype "passive"))
      (node (ref "R78") (pin "2") (pinfunction "2_2") (pintype "passive"))
    )
  )
)
